# OSSISolarY.net
KiCad netlist of a schematic drawn in EAGLE
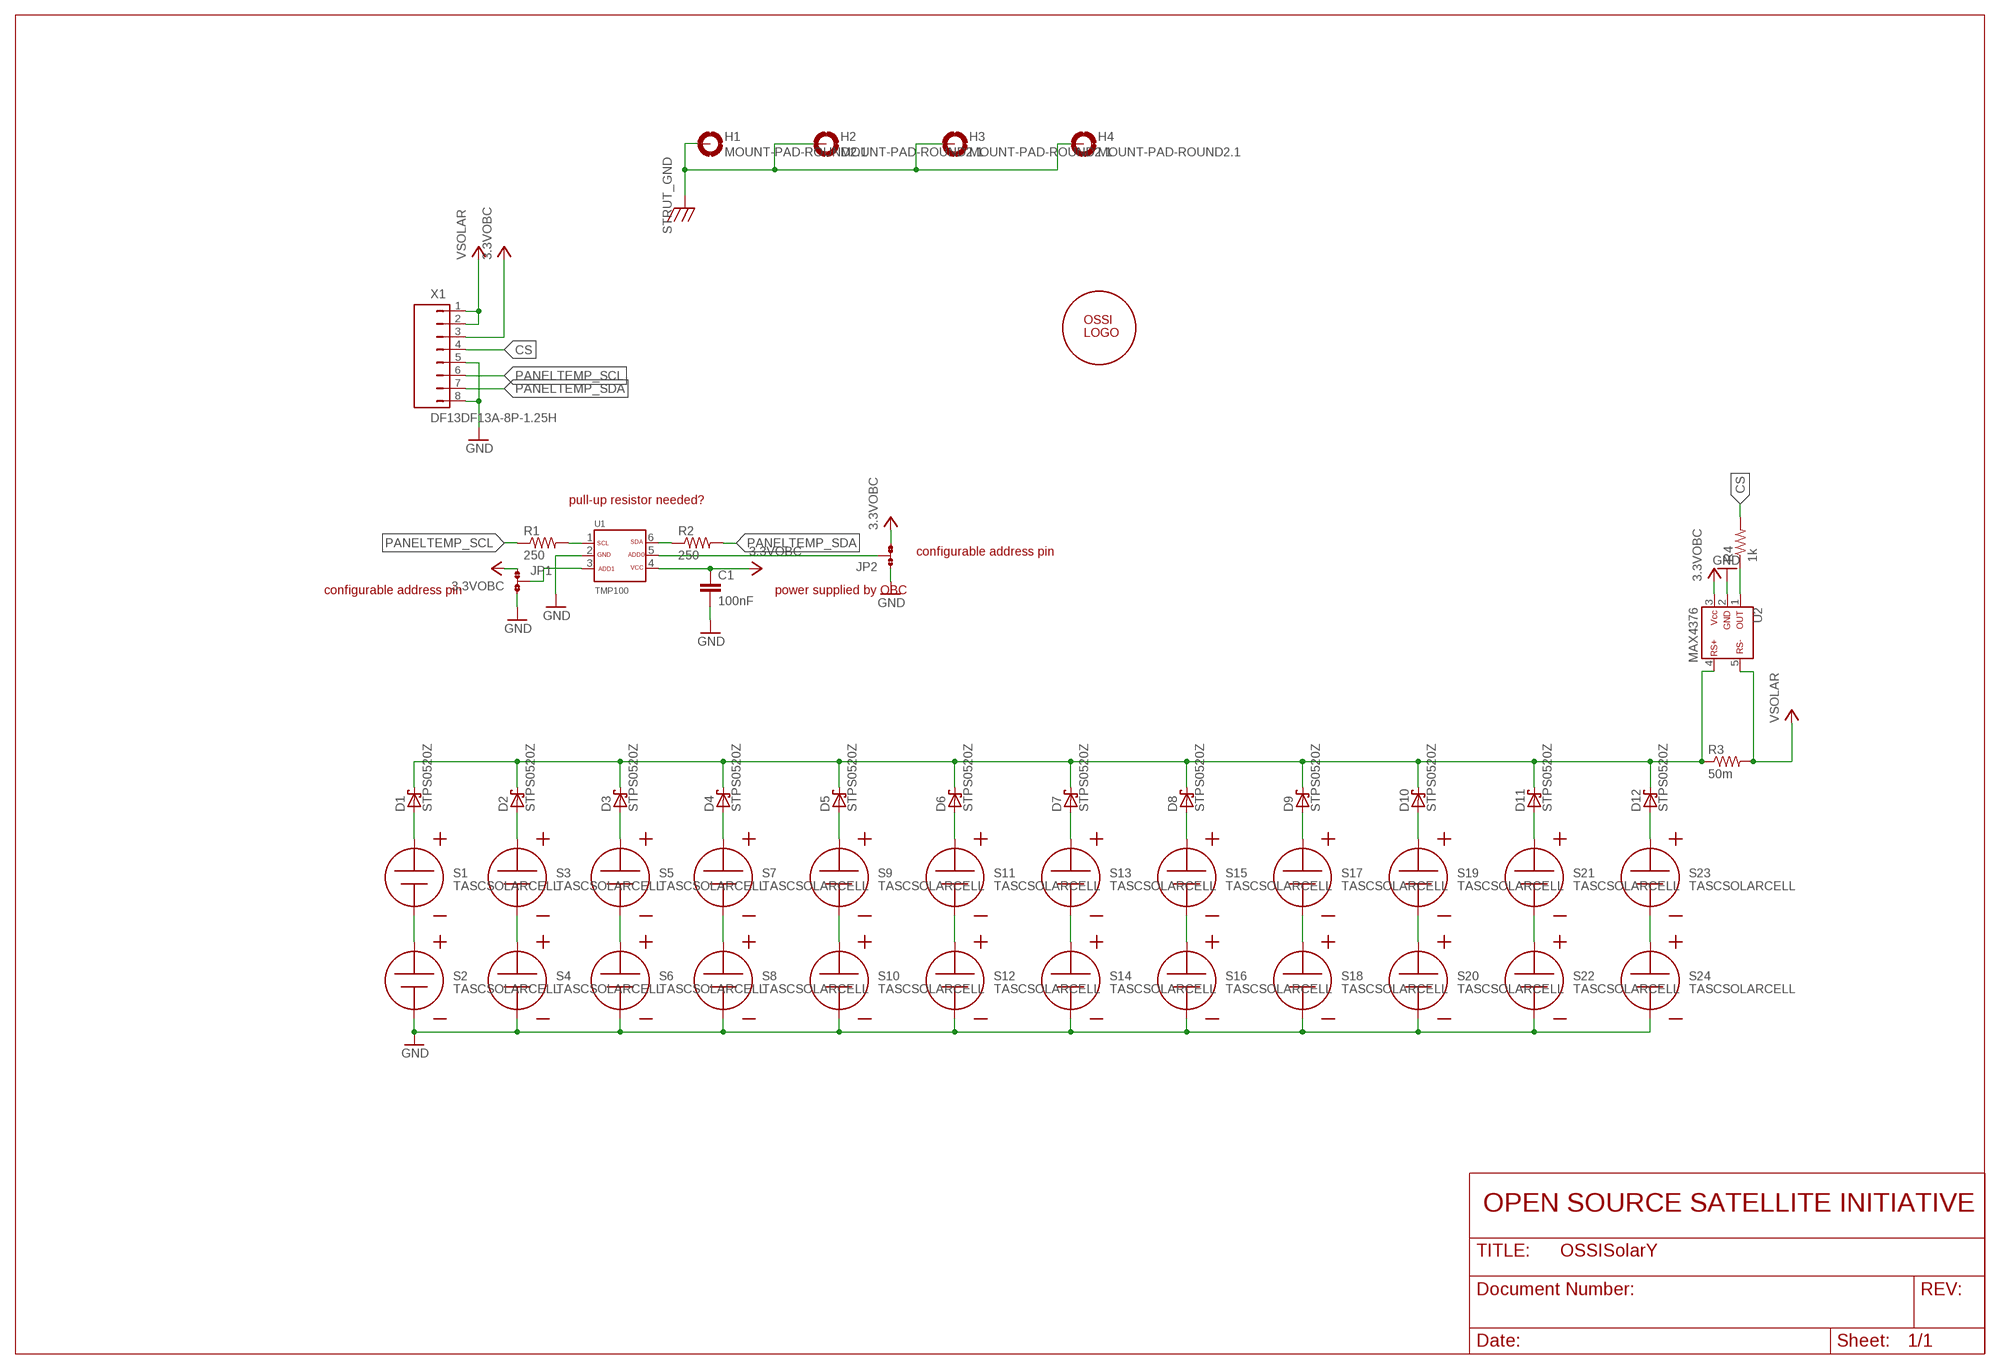
[diagram p0: schematic, sheet 1]

(export (version "E")
  (design (tool "Eeschema 10.0.6"))
  (components
    (comp (ref "C1")
      (value "100nF")
      (footprint "eagle-import:C0603(1608)")
      (libsource (lib "eagle-import") (part "C0603(1608)"))
    )
    (comp (ref "D1")
      (value "STPS0520Z")
      (footprint "eagle-import:SOD-123")
      (libsource (lib "eagle-import") (part "STPS0520Z"))
    )
    (comp (ref "D2")
      (value "STPS0520Z")
      (footprint "eagle-import:SOD-123")
      (libsource (lib "eagle-import") (part "STPS0520Z"))
    )
    (comp (ref "D3")
      (value "STPS0520Z")
      (footprint "eagle-import:SOD-123")
      (libsource (lib "eagle-import") (part "STPS0520Z"))
    )
    (comp (ref "D4")
      (value "STPS0520Z")
      (footprint "eagle-import:SOD-123")
      (libsource (lib "eagle-import") (part "STPS0520Z"))
    )
    (comp (ref "D5")
      (value "STPS0520Z")
      (footprint "eagle-import:SOD-123")
      (libsource (lib "eagle-import") (part "STPS0520Z"))
    )
    (comp (ref "D6")
      (value "STPS0520Z")
      (footprint "eagle-import:SOD-123")
      (libsource (lib "eagle-import") (part "STPS0520Z"))
    )
    (comp (ref "D7")
      (value "STPS0520Z")
      (footprint "eagle-import:SOD-123")
      (libsource (lib "eagle-import") (part "STPS0520Z"))
    )
    (comp (ref "D8")
      (value "STPS0520Z")
      (footprint "eagle-import:SOD-123")
      (libsource (lib "eagle-import") (part "STPS0520Z"))
    )
    (comp (ref "D9")
      (value "STPS0520Z")
      (footprint "eagle-import:SOD-123")
      (libsource (lib "eagle-import") (part "STPS0520Z"))
    )
    (comp (ref "D10")
      (value "STPS0520Z")
      (footprint "eagle-import:SOD-123")
      (libsource (lib "eagle-import") (part "STPS0520Z"))
    )
    (comp (ref "D11")
      (value "STPS0520Z")
      (footprint "eagle-import:SOD-123")
      (libsource (lib "eagle-import") (part "STPS0520Z"))
    )
    (comp (ref "D12")
      (value "STPS0520Z")
      (footprint "eagle-import:SOD-123")
      (libsource (lib "eagle-import") (part "STPS0520Z"))
    )
    (comp (ref "H1")
      (value "MOUNT-PAD-ROUND2.1")
      (footprint "eagle-import:2.1-PAD-ROUND")
      (libsource (lib "eagle-import") (part "MOUNT-PAD-ROUND2.1"))
    )
    (comp (ref "H2")
      (value "MOUNT-PAD-ROUND2.1")
      (footprint "eagle-import:2.1-PAD-ROUND")
      (libsource (lib "eagle-import") (part "MOUNT-PAD-ROUND2.1"))
    )
    (comp (ref "H3")
      (value "MOUNT-PAD-ROUND2.1")
      (footprint "eagle-import:2.1-PAD-ROUND")
      (libsource (lib "eagle-import") (part "MOUNT-PAD-ROUND2.1"))
    )
    (comp (ref "H4")
      (value "MOUNT-PAD-ROUND2.1")
      (footprint "eagle-import:2.1-PAD-ROUND")
      (libsource (lib "eagle-import") (part "MOUNT-PAD-ROUND2.1"))
    )
    (comp (ref "JP1")
      (value "JP2")
      (footprint "eagle-import:JP2SMD0603")
      (libsource (lib "eagle-import") (part "JP2"))
    )
    (comp (ref "JP2")
      (value "JP2")
      (footprint "eagle-import:JP2SMD0603")
      (libsource (lib "eagle-import") (part "JP2"))
    )
    (comp (ref "R1")
      (value "250")
      (footprint "eagle-import:R0603(1608)")
      (libsource (lib "eagle-import") (part "R0603(1608)"))
    )
    (comp (ref "R2")
      (value "250")
      (footprint "eagle-import:R0603(1608)")
      (libsource (lib "eagle-import") (part "R0603(1608)"))
    )
    (comp (ref "R3")
      (value "50m")
      (footprint "eagle-import:WSL1206")
      (libsource (lib "eagle-import") (part "RWSL1206"))
    )
    (comp (ref "R4")
      (value "1k")
      (footprint "eagle-import:R0603(1608)")
      (libsource (lib "eagle-import") (part "R0603(1608)"))
    )
    (comp (ref "S1")
      (value "TASCSOLARCELL")
      (footprint "eagle-import:TASCSOLARCELL")
      (libsource (lib "eagle-import") (part "TASCSOLARCELL"))
    )
    (comp (ref "S2")
      (value "TASCSOLARCELL")
      (footprint "eagle-import:TASCSOLARCELL")
      (libsource (lib "eagle-import") (part "TASCSOLARCELL"))
    )
    (comp (ref "S3")
      (value "TASCSOLARCELL")
      (footprint "eagle-import:TASCSOLARCELL")
      (libsource (lib "eagle-import") (part "TASCSOLARCELL"))
    )
    (comp (ref "S4")
      (value "TASCSOLARCELL")
      (footprint "eagle-import:TASCSOLARCELL")
      (libsource (lib "eagle-import") (part "TASCSOLARCELL"))
    )
    (comp (ref "S5")
      (value "TASCSOLARCELL")
      (footprint "eagle-import:TASCSOLARCELL")
      (libsource (lib "eagle-import") (part "TASCSOLARCELL"))
    )
    (comp (ref "S6")
      (value "TASCSOLARCELL")
      (footprint "eagle-import:TASCSOLARCELL")
      (libsource (lib "eagle-import") (part "TASCSOLARCELL"))
    )
    (comp (ref "S7")
      (value "TASCSOLARCELL")
      (footprint "eagle-import:TASCSOLARCELL")
      (libsource (lib "eagle-import") (part "TASCSOLARCELL"))
    )
    (comp (ref "S8")
      (value "TASCSOLARCELL")
      (footprint "eagle-import:TASCSOLARCELL")
      (libsource (lib "eagle-import") (part "TASCSOLARCELL"))
    )
    (comp (ref "S9")
      (value "TASCSOLARCELL")
      (footprint "eagle-import:TASCSOLARCELL")
      (libsource (lib "eagle-import") (part "TASCSOLARCELL"))
    )
    (comp (ref "S10")
      (value "TASCSOLARCELL")
      (footprint "eagle-import:TASCSOLARCELL")
      (libsource (lib "eagle-import") (part "TASCSOLARCELL"))
    )
    (comp (ref "S11")
      (value "TASCSOLARCELL")
      (footprint "eagle-import:TASCSOLARCELL")
      (libsource (lib "eagle-import") (part "TASCSOLARCELL"))
    )
    (comp (ref "S12")
      (value "TASCSOLARCELL")
      (footprint "eagle-import:TASCSOLARCELL")
      (libsource (lib "eagle-import") (part "TASCSOLARCELL"))
    )
    (comp (ref "S13")
      (value "TASCSOLARCELL")
      (footprint "eagle-import:TASCSOLARCELL")
      (libsource (lib "eagle-import") (part "TASCSOLARCELL"))
    )
    (comp (ref "S14")
      (value "TASCSOLARCELL")
      (footprint "eagle-import:TASCSOLARCELL")
      (libsource (lib "eagle-import") (part "TASCSOLARCELL"))
    )
    (comp (ref "S15")
      (value "TASCSOLARCELL")
      (footprint "eagle-import:TASCSOLARCELL")
      (libsource (lib "eagle-import") (part "TASCSOLARCELL"))
    )
    (comp (ref "S16")
      (value "TASCSOLARCELL")
      (footprint "eagle-import:TASCSOLARCELL")
      (libsource (lib "eagle-import") (part "TASCSOLARCELL"))
    )
    (comp (ref "S17")
      (value "TASCSOLARCELL")
      (footprint "eagle-import:TASCSOLARCELL")
      (libsource (lib "eagle-import") (part "TASCSOLARCELL"))
    )
    (comp (ref "S18")
      (value "TASCSOLARCELL")
      (footprint "eagle-import:TASCSOLARCELL")
      (libsource (lib "eagle-import") (part "TASCSOLARCELL"))
    )
    (comp (ref "S19")
      (value "TASCSOLARCELL")
      (footprint "eagle-import:TASCSOLARCELL")
      (libsource (lib "eagle-import") (part "TASCSOLARCELL"))
    )
    (comp (ref "S20")
      (value "TASCSOLARCELL")
      (footprint "eagle-import:TASCSOLARCELL")
      (libsource (lib "eagle-import") (part "TASCSOLARCELL"))
    )
    (comp (ref "S21")
      (value "TASCSOLARCELL")
      (footprint "eagle-import:TASCSOLARCELL")
      (libsource (lib "eagle-import") (part "TASCSOLARCELL"))
    )
    (comp (ref "S22")
      (value "TASCSOLARCELL")
      (footprint "eagle-import:TASCSOLARCELL")
      (libsource (lib "eagle-import") (part "TASCSOLARCELL"))
    )
    (comp (ref "S23")
      (value "TASCSOLARCELL")
      (footprint "eagle-import:TASCSOLARCELL")
      (libsource (lib "eagle-import") (part "TASCSOLARCELL"))
    )
    (comp (ref "S24")
      (value "TASCSOLARCELL")
      (footprint "eagle-import:TASCSOLARCELL")
      (libsource (lib "eagle-import") (part "TASCSOLARCELL"))
    )
    (comp (ref "U$2")
      (value "OSSILOGO")
      (footprint "eagle-import:OSSILOGORECT1005")
      (libsource (lib "eagle-import") (part "OSSILOGO"))
    )
    (comp (ref "U1")
      (value "TMP100")
      (footprint "eagle-import:SOT23-6DBV")
      (libsource (lib "eagle-import") (part "TMP100"))
    )
    (comp (ref "U2")
      (value "MAX4376")
      (footprint "eagle-import:SOT23-5DBV")
      (libsource (lib "eagle-import") (part "MAX4376"))
    )
    (comp (ref "X1")
      (value "DF13DF13A-8P-1.25H")
      (footprint "eagle-import:DF13A-8P")
      (libsource (lib "eagle-import") (part "DF13DF13A-8P-1.25H"))
    )
  )
  (nets
    (net (code "1") (name "3.3VOBC") (class "Default")
      (node (ref "C1") (pin "1") (pinfunction "1_1") (pintype "passive"))
      (node (ref "JP1") (pin "1") (pinfunction "1_1") (pintype "passive"))
      (node (ref "JP2") (pin "3") (pinfunction "3_3") (pintype "passive"))
      (node (ref "U1") (pin "4") (pinfunction "4_4") (pintype "bidirectional"))
      (node (ref "U2") (pin "3") (pinfunction "P$3_3") (pintype "power_in"))
      (node (ref "X1") (pin "3") (pinfunction "3_3") (pintype "passive"))
    )
    (net (code "2") (name "CS") (class "Default")
      (node (ref "R4") (pin "2") (pinfunction "2_2") (pintype "passive"))
      (node (ref "X1") (pin "4") (pinfunction "4_4") (pintype "passive"))
    )
    (net (code "3") (name "GND") (class "Default")
      (node (ref "C1") (pin "2") (pinfunction "2_2") (pintype "passive"))
      (node (ref "JP1") (pin "3") (pinfunction "3_3") (pintype "passive"))
      (node (ref "JP2") (pin "1") (pinfunction "1_1") (pintype "passive"))
      (node (ref "S10") (pin "N") (pinfunction "N_N") (pintype "power_in"))
      (node (ref "S12") (pin "N") (pinfunction "N_N") (pintype "power_in"))
      (node (ref "S14") (pin "N") (pinfunction "N_N") (pintype "power_in"))
      (node (ref "S16") (pin "N") (pinfunction "N_N") (pintype "power_in"))
      (node (ref "S18") (pin "N") (pinfunction "N_N") (pintype "power_in"))
      (node (ref "S2") (pin "N") (pinfunction "N_N") (pintype "power_in"))
      (node (ref "S20") (pin "N") (pinfunction "N_N") (pintype "power_in"))
      (node (ref "S22") (pin "N") (pinfunction "N_N") (pintype "power_in"))
      (node (ref "S24") (pin "N") (pinfunction "N_N") (pintype "power_in"))
      (node (ref "S4") (pin "N") (pinfunction "N_N") (pintype "power_in"))
      (node (ref "S6") (pin "N") (pinfunction "N_N") (pintype "power_in"))
      (node (ref "S8") (pin "N") (pinfunction "N_N") (pintype "power_in"))
      (node (ref "U1") (pin "2") (pinfunction "2_2") (pintype "bidirectional"))
      (node (ref "U2") (pin "2") (pinfunction "P$2_2") (pintype "power_in"))
      (node (ref "X1") (pin "5") (pinfunction "5_5") (pintype "passive"))
      (node (ref "X1") (pin "8") (pinfunction "8_8") (pintype "passive"))
    )
    (net (code "4") (name "Net-(D1-PadA)") (class "Default")
      (node (ref "D1") (pin "A") (pinfunction "A_A") (pintype "passive"))
      (node (ref "S1") (pin "P") (pinfunction "P_P") (pintype "power_in"))
    )
    (net (code "5") (name "Net-(D2-PadA)") (class "Default")
      (node (ref "D2") (pin "A") (pinfunction "A_A") (pintype "passive"))
      (node (ref "S3") (pin "P") (pinfunction "P_P") (pintype "power_in"))
    )
    (net (code "6") (name "Net-(D3-PadA)") (class "Default")
      (node (ref "D3") (pin "A") (pinfunction "A_A") (pintype "passive"))
      (node (ref "S5") (pin "P") (pinfunction "P_P") (pintype "power_in"))
    )
    (net (code "7") (name "Net-(D4-PadA)") (class "Default")
      (node (ref "D4") (pin "A") (pinfunction "A_A") (pintype "passive"))
      (node (ref "S7") (pin "P") (pinfunction "P_P") (pintype "power_in"))
    )
    (net (code "8") (name "Net-(D5-PadA)") (class "Default")
      (node (ref "D5") (pin "A") (pinfunction "A_A") (pintype "passive"))
      (node (ref "S9") (pin "P") (pinfunction "P_P") (pintype "power_in"))
    )
    (net (code "9") (name "Net-(D6-PadA)") (class "Default")
      (node (ref "D6") (pin "A") (pinfunction "A_A") (pintype "passive"))
      (node (ref "S11") (pin "P") (pinfunction "P_P") (pintype "power_in"))
    )
    (net (code "10") (name "Net-(D7-PadA)") (class "Default")
      (node (ref "D7") (pin "A") (pinfunction "A_A") (pintype "passive"))
      (node (ref "S13") (pin "P") (pinfunction "P_P") (pintype "power_in"))
    )
    (net (code "11") (name "Net-(D8-PadA)") (class "Default")
      (node (ref "D8") (pin "A") (pinfunction "A_A") (pintype "passive"))
      (node (ref "S15") (pin "P") (pinfunction "P_P") (pintype "power_in"))
    )
    (net (code "12") (name "Net-(D9-PadA)") (class "Default")
      (node (ref "D9") (pin "A") (pinfunction "A_A") (pintype "passive"))
      (node (ref "S17") (pin "P") (pinfunction "P_P") (pintype "power_in"))
    )
    (net (code "13") (name "Net-(D10-PadA)") (class "Default")
      (node (ref "D10") (pin "A") (pinfunction "A_A") (pintype "passive"))
      (node (ref "S19") (pin "P") (pinfunction "P_P") (pintype "power_in"))
    )
    (net (code "14") (name "Net-(D11-PadA)") (class "Default")
      (node (ref "D11") (pin "A") (pinfunction "A_A") (pintype "passive"))
      (node (ref "S21") (pin "P") (pinfunction "P_P") (pintype "power_in"))
    )
    (net (code "15") (name "Net-(D12-PadA)") (class "Default")
      (node (ref "D12") (pin "A") (pinfunction "A_A") (pintype "passive"))
      (node (ref "S23") (pin "P") (pinfunction "P_P") (pintype "power_in"))
    )
    (net (code "16") (name "Net-(JP1-Pad2)") (class "Default")
      (node (ref "JP1") (pin "2") (pinfunction "2_2") (pintype "passive"))
      (node (ref "U1") (pin "3") (pinfunction "3_3") (pintype "bidirectional"))
    )
    (net (code "17") (name "Net-(JP2-Pad2)") (class "Default")
      (node (ref "JP2") (pin "2") (pinfunction "2_2") (pintype "passive"))
      (node (ref "U1") (pin "5") (pinfunction "5_5") (pintype "bidirectional"))
    )
    (net (code "18") (name "Net-(R1-Pad2)") (class "Default")
      (node (ref "R1") (pin "2") (pinfunction "2_2") (pintype "passive"))
      (node (ref "U1") (pin "1") (pinfunction "1_1") (pintype "bidirectional"))
    )
    (net (code "19") (name "Net-(R2-Pad1)") (class "Default")
      (node (ref "R2") (pin "1") (pinfunction "1_1") (pintype "passive"))
      (node (ref "U1") (pin "6") (pinfunction "6_6") (pintype "bidirectional"))
    )
    (net (code "20") (name "Net-(R3-1)") (class "Default")
      (node (ref "D1") (pin "C") (pinfunction "C_C") (pintype "passive"))
      (node (ref "D10") (pin "C") (pinfunction "C_C") (pintype "passive"))
      (node (ref "D11") (pin "C") (pinfunction "C_C") (pintype "passive"))
      (node (ref "D12") (pin "C") (pinfunction "C_C") (pintype "passive"))
      (node (ref "D2") (pin "C") (pinfunction "C_C") (pintype "passive"))
      (node (ref "D3") (pin "C") (pinfunction "C_C") (pintype "passive"))
      (node (ref "D4") (pin "C") (pinfunction "C_C") (pintype "passive"))
      (node (ref "D5") (pin "C") (pinfunction "C_C") (pintype "passive"))
      (node (ref "D6") (pin "C") (pinfunction "C_C") (pintype "passive"))
      (node (ref "D7") (pin "C") (pinfunction "C_C") (pintype "passive"))
      (node (ref "D8") (pin "C") (pinfunction "C_C") (pintype "passive"))
      (node (ref "D9") (pin "C") (pinfunction "C_C") (pintype "passive"))
      (node (ref "R3") (pin "P$1") (pinfunction "1_P$1") (pintype "passive"))
      (node (ref "U2") (pin "4") (pinfunction "P$4_4") (pintype "input"))
    )
    (net (code "21") (name "Net-(S1-PadN)") (class "Default")
      (node (ref "S1") (pin "N") (pinfunction "N_N") (pintype "power_in"))
      (node (ref "S2") (pin "P") (pinfunction "P_P") (pintype "power_in"))
    )
    (net (code "22") (name "Net-(S3-PadN)") (class "Default")
      (node (ref "S3") (pin "N") (pinfunction "N_N") (pintype "power_in"))
      (node (ref "S4") (pin "P") (pinfunction "P_P") (pintype "power_in"))
    )
    (net (code "23") (name "Net-(S5-PadN)") (class "Default")
      (node (ref "S5") (pin "N") (pinfunction "N_N") (pintype "power_in"))
      (node (ref "S6") (pin "P") (pinfunction "P_P") (pintype "power_in"))
    )
    (net (code "24") (name "Net-(S7-PadN)") (class "Default")
      (node (ref "S7") (pin "N") (pinfunction "N_N") (pintype "power_in"))
      (node (ref "S8") (pin "P") (pinfunction "P_P") (pintype "power_in"))
    )
    (net (code "25") (name "Net-(S10-PadP)") (class "Default")
      (node (ref "S10") (pin "P") (pinfunction "P_P") (pintype "power_in"))
      (node (ref "S9") (pin "N") (pinfunction "N_N") (pintype "power_in"))
    )
    (net (code "26") (name "Net-(S11-PadN)") (class "Default")
      (node (ref "S11") (pin "N") (pinfunction "N_N") (pintype "power_in"))
      (node (ref "S12") (pin "P") (pinfunction "P_P") (pintype "power_in"))
    )
    (net (code "27") (name "Net-(S13-PadN)") (class "Default")
      (node (ref "S13") (pin "N") (pinfunction "N_N") (pintype "power_in"))
      (node (ref "S14") (pin "P") (pinfunction "P_P") (pintype "power_in"))
    )
    (net (code "28") (name "Net-(S15-PadN)") (class "Default")
      (node (ref "S15") (pin "N") (pinfunction "N_N") (pintype "power_in"))
      (node (ref "S16") (pin "P") (pinfunction "P_P") (pintype "power_in"))
    )
    (net (code "29") (name "Net-(S17-PadN)") (class "Default")
      (node (ref "S17") (pin "N") (pinfunction "N_N") (pintype "power_in"))
      (node (ref "S18") (pin "P") (pinfunction "P_P") (pintype "power_in"))
    )
    (net (code "30") (name "Net-(S19-PadN)") (class "Default")
      (node (ref "S19") (pin "N") (pinfunction "N_N") (pintype "power_in"))
      (node (ref "S20") (pin "P") (pinfunction "P_P") (pintype "power_in"))
    )
    (net (code "31") (name "Net-(S21-PadN)") (class "Default")
      (node (ref "S21") (pin "N") (pinfunction "N_N") (pintype "power_in"))
      (node (ref "S22") (pin "P") (pinfunction "P_P") (pintype "power_in"))
    )
    (net (code "32") (name "Net-(S23-PadN)") (class "Default")
      (node (ref "S23") (pin "N") (pinfunction "N_N") (pintype "power_in"))
      (node (ref "S24") (pin "P") (pinfunction "P_P") (pintype "power_in"))
    )
    (net (code "33") (name "Net-(U2-P$1)") (class "Default")
      (node (ref "R4") (pin "1") (pinfunction "1_1") (pintype "passive"))
      (node (ref "U2") (pin "1") (pinfunction "P$1_1") (pintype "output"))
    )
    (net (code "34") (name "PANELTEMP_SCL") (class "Default")
      (node (ref "R1") (pin "1") (pinfunction "1_1") (pintype "passive"))
      (node (ref "X1") (pin "6") (pinfunction "6_6") (pintype "passive"))
    )
    (net (code "35") (name "PANELTEMP_SDA") (class "Default")
      (node (ref "R2") (pin "2") (pinfunction "2_2") (pintype "passive"))
      (node (ref "X1") (pin "7") (pinfunction "7_7") (pintype "passive"))
    )
    (net (code "36") (name "STRUT_GND") (class "Default")
      (node (ref "H1") (pin "B3,2") (pinfunction "MOUNT_B3,2") (pintype "passive"))
      (node (ref "H2") (pin "B3,2") (pinfunction "MOUNT_B3,2") (pintype "passive"))
      (node (ref "H3") (pin "B3,2") (pinfunction "MOUNT_B3,2") (pintype "passive"))
      (node (ref "H4") (pin "B3,2") (pinfunction "MOUNT_B3,2") (pintype "passive"))
    )
    (net (code "37") (name "VSOLAR") (class "Default")
      (node (ref "R3") (pin "P$2") (pinfunction "2_P$2") (pintype "passive"))
      (node (ref "U2") (pin "5") (pinfunction "P$5_5") (pintype "input"))
      (node (ref "X1") (pin "1") (pinfunction "1_1") (pintype "passive"))
      (node (ref "X1") (pin "2") (pinfunction "2_2") (pintype "passive"))
    )
  )
)
